# 4_Sensoren.net
KiCad netlist of a schematic drawn in Altium Designer
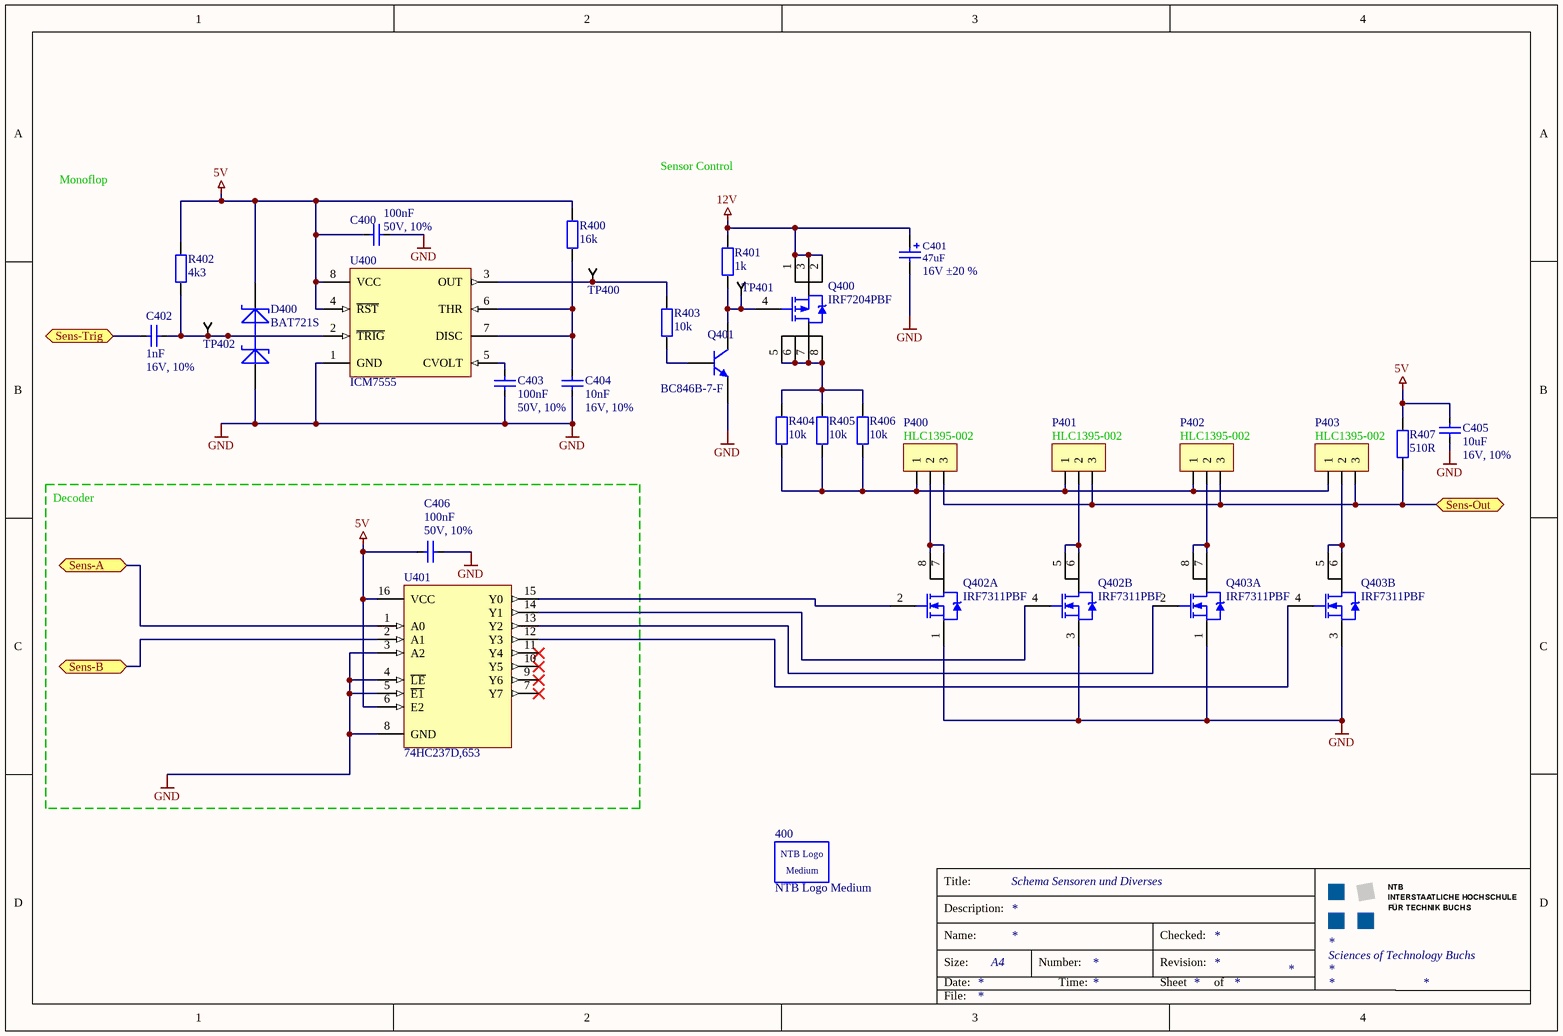
[diagram p0: 4_Sensoren.SchDoc]

(export (version "E")
  (design (tool "Eeschema 10.0.6"))
  (components
    (comp (ref "400")
      (value "NTB Logo Medium")
      (footprint "NTB Logo Medium")
      (libsource (lib "IR-Sensor") (part "NTB Logo Medium"))
    )
    (comp (ref "C400")
      (value "100nF")
      (footprint "CAP-0805[2012]")
      (description "100n 50V X7R MLCC 0805 (1608 Metric)")
      (fields (field (name "TOLERANCE") "10%") (field (name "VALADDON") "50V, 10%"))
      (libsource (lib "IR-Sensor") (part "MLCC 0805 100n 50V"))
    )
    (comp (ref "C401")
      (value "47uF")
      (footprint "CDE_CAP AVE CODE D_H")
      (description "ELKO, 47uF, 16V, CDE_AVE476M16D16T-F_AVE CODE D")
      (fields
        (field (name "MANUFACTURER") "Cornell Dubilier")
        (field (name "VALUEADDON") "16V ±20 %")
        (field (name "Comment") "AVE476M16D16T-F")
        (field (name "PUBLISHER") "Stefan Ursella, M.Eng")
      )
      (libsource (lib "IR-Sensor") (part "ELKO 47uF 16V"))
    )
    (comp (ref "C402")
      (value "1nF")
      (footprint "CAP-0805[2012]")
      (description "MLCC - SMD/SMT 0805 1000pF 16V C0G 10%")
      (fields
        (field (name "MANUFACTURER") "Vishay")
        (field (name "VALUEADDON") "16V, 10%")
        (field (name "PUBLISHER") "SCLM")
      )
      (libsource (lib "IR-Sensor") (part "MLCC 0805 1n 16V"))
    )
    (comp (ref "C403")
      (value "100nF")
      (footprint "CAP-0805[2012]")
      (description "100n 50V X7R MLCC 0805 (1608 Metric)")
      (fields (field (name "TOLERANCE") "10%") (field (name "VALADDON") "50V, 10%"))
      (libsource (lib "IR-Sensor") (part "MLCC 0805 100n 50V"))
    )
    (comp (ref "C404")
      (value "10nF")
      (footprint "CAP-0805[2012]")
      (description "10n 16V X7R MLCC 0805")
      (fields
        (field (name "MANUFACTURER") "AVX")
        (field (name "VALUEADDON") "16V, 10%")
        (field (name "PUBLISHER") "SCLM")
      )
      (libsource (lib "IR-Sensor") (part "MLCC 0805 10n 16V"))
    )
    (comp (ref "C405")
      (value "10uF")
      (footprint "CAP-1206[3216]")
      (description "10u 16V X7R MLCC 1206 (3016 Metric)")
      (fields (field (name "TOLERANCE") "10%") (field (name "VALADDON") "16V, 10%"))
      (libsource (lib "IR-Sensor") (part "MLCC 1206 10u 16V"))
    )
    (comp (ref "C406")
      (value "100nF")
      (footprint "CAP-0805[2012]")
      (description "100n 50V X7R MLCC 0805 (1608 Metric)")
      (fields (field (name "TOLERANCE") "10%") (field (name "VALADDON") "50V, 10%"))
      (libsource (lib "IR-Sensor") (part "MLCC 0805 100n 50V"))
    )
    (comp (ref "D400")
      (value "BAT721S")
      (footprint "SOT-23")
      (description "NXP  BAT721S  SCHOTTKY-DIODE, 2FACH")
      (fields (field (name "MANUFACTURER") "NXP") (field (name "PUBLISHER") "SCNP"))
      (libsource (lib "IR-Sensor") (part "BAT721S-SOT23"))
    )
    (comp (ref "P400")
      (value "3 Pin Header Buchse")
      (footprint "3PIN HEADER SOCKET 2.54MM")
      (description "3 Pin Header 2.54mm Buchse")
      (libsource (lib "IR-Sensor") (part "3 Pin Header Buchse"))
    )
    (comp (ref "P401")
      (value "3 Pin Header Buchse")
      (footprint "3PIN HEADER SOCKET 2.54MM")
      (description "3 Pin Header 2.54mm Buchse")
      (libsource (lib "IR-Sensor") (part "3 Pin Header Buchse"))
    )
    (comp (ref "P402")
      (value "3 Pin Header Buchse")
      (footprint "3PIN HEADER SOCKET 2.54MM")
      (description "3 Pin Header 2.54mm Buchse")
      (libsource (lib "IR-Sensor") (part "3 Pin Header Buchse"))
    )
    (comp (ref "P403")
      (value "3 Pin Header Buchse")
      (footprint "3PIN HEADER SOCKET 2.54MM")
      (description "3 Pin Header 2.54mm Buchse")
      (libsource (lib "IR-Sensor") (part "3 Pin Header Buchse"))
    )
    (comp (ref "Q400")
      (value "IRF7204PBF")
      (footprint "SOIC-8")
      (description "High Power P-Kanal Mosfet")
      (fields
        (field (name "MANUFACTURER") "International Rectifiers")
        (field (name "PUBLISHER") "Altium Limited")
      )
      (libsource (lib "IR-Sensor") (part "IRF7204"))
    )
    (comp (ref "Q401")
      (value "BC846B-7-F")
      (footprint "SOT-23")
      (description "NPN General-purpose Transistor")
      (fields (field (name "MANUFACTURER") "DIODES INC") (field (name "PUBLISHER") "Altium Limited"))
      (libsource (lib "IR-Sensor") (part "BC846B-SOT23"))
    )
    (comp (ref "Q402")
      (value "IRF7311PBF")
      (footprint "SOIC-8")
      (description "Dual N-Kanal Mosfet")
      (fields
        (field (name "MANUFACTURER") "International Rectifier")
        (field (name "PUBLISHER") "Altium Limited")
      )
      (libsource (lib "IR-Sensor") (part "IRF7311"))
    )
    (comp (ref "Q403")
      (value "IRF7311PBF")
      (footprint "SOIC-8")
      (description "Dual N-Kanal Mosfet")
      (fields
        (field (name "MANUFACTURER") "International Rectifier")
        (field (name "PUBLISHER") "Altium Limited")
      )
      (libsource (lib "IR-Sensor") (part "IRF7311"))
    )
    (comp (ref "R400")
      (value "16k")
      (footprint "RES-0805[2012]")
      (description "0805 (2013 Metric) 1/10 W 10K 1 Thick Film Chip Resistor")
      (fields (field (name "POWER") "1/10 W") (field (name "TOLERANCE") "1%"))
      (libsource (lib "IR-Sensor") (part "RES 0805"))
    )
    (comp (ref "R401")
      (value "1k")
      (footprint "RES-0805[2012]")
      (description "0805 (2013 Metric) 1/10 W 10K 1 Thick Film Chip Resistor")
      (fields (field (name "POWER") "1/10 W") (field (name "TOLERANCE") "1%"))
      (libsource (lib "IR-Sensor") (part "RES 0805"))
    )
    (comp (ref "R402")
      (value "4k3")
      (footprint "RES-0805[2012]")
      (description "0805 (2013 Metric) 1/10 W 10K 1 Thick Film Chip Resistor")
      (fields (field (name "POWER") "1/10 W") (field (name "TOLERANCE") "1%"))
      (libsource (lib "IR-Sensor") (part "RES 0805"))
    )
    (comp (ref "R403")
      (value "10k")
      (footprint "RES-0805[2012]")
      (description "0805 (2013 Metric) 1/10 W 10K 1 Thick Film Chip Resistor")
      (fields (field (name "POWER") "1/10 W") (field (name "TOLERANCE") "1%"))
      (libsource (lib "IR-Sensor") (part "RES 0805"))
    )
    (comp (ref "R404")
      (value "10k")
      (footprint "RES-0805[2012]")
      (description "0805 (2013 Metric) 1/10 W 10K 1 Thick Film Chip Resistor")
      (fields (field (name "POWER") "1/10 W") (field (name "TOLERANCE") "1%"))
      (libsource (lib "IR-Sensor") (part "RES 0805"))
    )
    (comp (ref "R405")
      (value "10k")
      (footprint "RES-0805[2012]")
      (description "0805 (2013 Metric) 1/10 W 10K 1 Thick Film Chip Resistor")
      (fields (field (name "POWER") "1/10 W") (field (name "TOLERANCE") "1%"))
      (libsource (lib "IR-Sensor") (part "RES 0805"))
    )
    (comp (ref "R406")
      (value "10k")
      (footprint "RES-0805[2012]")
      (description "0805 (2013 Metric) 1/10 W 10K 1 Thick Film Chip Resistor")
      (fields (field (name "POWER") "1/10 W") (field (name "TOLERANCE") "1%"))
      (libsource (lib "IR-Sensor") (part "RES 0805"))
    )
    (comp (ref "R407")
      (value "510R")
      (footprint "RES-0805[2012]")
      (description "0805 (2013 Metric) 1/10 W 10K 1 Thick Film Chip Resistor")
      (fields (field (name "POWER") "1/10 W") (field (name "TOLERANCE") "1%"))
      (libsource (lib "IR-Sensor") (part "RES 0805"))
    )
    (comp (ref "TP400")
      (value "Testpoint SMD 1206")
      (footprint "TP-SMD-1206")
      (description "Testpoint xSmall")
      (libsource (lib "IR-Sensor") (part "Testpoint SMD 1206"))
    )
    (comp (ref "TP401")
      (value "Testpoint SMD 1206")
      (footprint "TP-SMD-1206")
      (description "Testpoint xSmall")
      (libsource (lib "altium-import") (part "root_0_Testpoint SMD 1206_"))
    )
    (comp (ref "TP402")
      (value "Testpoint SMD 1206")
      (footprint "TP-SMD-1206")
      (description "Testpoint xSmall")
      (libsource (lib "IR-Sensor") (part "Testpoint SMD 1206"))
    )
    (comp (ref "U400")
      (value "ICM7555")
      (footprint "SOIC-8")
      (description "General purpose CMOS timer")
      (fields
        (field (name "MANUFACTURER") "National Semiconductor")
        (field (name "PUBLISHER") "Altium Hobart Technology Centre")
      )
      (libsource (lib "IR-Sensor") (part "ICM7555-SOIC8"))
    )
    (comp (ref "U401")
      (value "74HC237D,653")
      (footprint "SOIC-16")
      (description "3-to-8 line decoder, demultiplexer, NXP, SO16")
      (fields (field (name "MANUFACTURER") "NXP") (field (name "PUBLISHER") "SCLM"))
      (libsource (lib "IR-Sensor") (part "74HC237D-SOIC16"))
    )
  )
  (nets
    (net (code "1") (name "/Sens-A") (class "Default")
      (node (ref "U401") (pin "1") (pinfunction "A0_1") (pintype "input"))
    )
    (net (code "2") (name "/Sens-B") (class "Default")
      (node (ref "U401") (pin "2") (pinfunction "A1_2") (pintype "input"))
    )
    (net (code "3") (name "/Sens-Out") (class "Default")
      (node (ref "P400") (pin "3") (pinfunction "3_3") (pintype "passive"))
      (node (ref "P401") (pin "3") (pinfunction "3_3") (pintype "passive"))
      (node (ref "P402") (pin "3") (pinfunction "3_3") (pintype "passive"))
      (node (ref "P403") (pin "3") (pinfunction "3_3") (pintype "passive"))
      (node (ref "R407") (pin "1") (pinfunction "1_1") (pintype "passive"))
    )
    (net (code "4") (name "/Sens-Trig") (class "Default")
      (node (ref "C402") (pin "1") (pinfunction "Pos_1") (pintype "passive"))
    )
    (net (code "5") (name "5V") (class "Default")
      (node (ref "C400") (pin "1") (pinfunction "Pos_1") (pintype "passive"))
      (node (ref "C405") (pin "1") (pinfunction "Pos_1") (pintype "passive"))
      (node (ref "C406") (pin "1") (pinfunction "Pos_1") (pintype "passive"))
      (node (ref "D400") (pin "2") (pinfunction "cathode2_2") (pintype "passive"))
      (node (ref "R400") (pin "2") (pinfunction "2_2") (pintype "passive"))
      (node (ref "R402") (pin "2") (pinfunction "2_2") (pintype "passive"))
      (node (ref "R407") (pin "2") (pinfunction "2_2") (pintype "passive"))
      (node (ref "U400") (pin "4") (pinfunction "~{RST}_4") (pintype "input"))
      (node (ref "U400") (pin "8") (pinfunction "VCC_8") (pintype "power_in"))
      (node (ref "U401") (pin "16") (pinfunction "VCC_16") (pintype "power_in"))
      (node (ref "U401") (pin "6") (pinfunction "E2_6") (pintype "input"))
    )
    (net (code "6") (name "12V") (class "Default")
      (node (ref "C401") (pin "1") (pinfunction "Pos_1") (pintype "passive"))
      (node (ref "Q400") (pin "1") (pinfunction "S_1") (pintype "passive"))
      (node (ref "Q400") (pin "2") (pinfunction "S_2") (pintype "passive"))
      (node (ref "Q400") (pin "3") (pinfunction "S_3") (pintype "passive"))
      (node (ref "R401") (pin "2") (pinfunction "2_2") (pintype "passive"))
    )
    (net (code "7") (name "GND") (class "Default")
      (node (ref "C400") (pin "2") (pinfunction "Neg_2") (pintype "passive"))
      (node (ref "C401") (pin "2") (pinfunction "Neg_2") (pintype "passive"))
      (node (ref "C403") (pin "2") (pinfunction "Neg_2") (pintype "passive"))
      (node (ref "C404") (pin "2") (pinfunction "Neg_2") (pintype "passive"))
      (node (ref "C405") (pin "2") (pinfunction "Neg_2") (pintype "passive"))
      (node (ref "C406") (pin "2") (pinfunction "Neg_2") (pintype "passive"))
      (node (ref "D400") (pin "1") (pinfunction "Anode1_1") (pintype "passive"))
      (node (ref "Q401") (pin "2") (pinfunction "E_2") (pintype "passive"))
      (node (ref "Q402") (pin "1") (pinfunction "S_1") (pintype "passive"))
      (node (ref "Q402") (pin "3") (pinfunction "S_3") (pintype "passive"))
      (node (ref "Q403") (pin "1") (pinfunction "S_1") (pintype "passive"))
      (node (ref "Q403") (pin "3") (pinfunction "S_3") (pintype "passive"))
      (node (ref "U400") (pin "1") (pinfunction "GND_1") (pintype "power_in"))
      (node (ref "U401") (pin "3") (pinfunction "A2_3") (pintype "input"))
      (node (ref "U401") (pin "4") (pinfunction "LE_4") (pintype "input"))
      (node (ref "U401") (pin "5") (pinfunction "E1_5") (pintype "input"))
      (node (ref "U401") (pin "8") (pinfunction "GND_8") (pintype "power_in"))
    )
    (net (code "8") (name "Net-(C402-Neg)") (class "Default")
      (node (ref "C402") (pin "2") (pinfunction "Neg_2") (pintype "passive"))
      (node (ref "D400") (pin "3") (pinfunction "Cathode1,_anode2_3") (pintype "passive"))
      (node (ref "R402") (pin "1") (pinfunction "1_1") (pintype "passive"))
      (node (ref "TP402") (pin "1") (pinfunction "0_1") (pintype "passive"))
      (node (ref "U400") (pin "2") (pinfunction "TRIG_2") (pintype "input"))
    )
    (net (code "9") (name "Net-(C403-Pos)") (class "Default")
      (node (ref "C403") (pin "1") (pinfunction "Pos_1") (pintype "passive"))
      (node (ref "U400") (pin "5") (pinfunction "CVOLT_5") (pintype "input"))
    )
    (net (code "10") (name "Net-(C404-Pos)") (class "Default")
      (node (ref "C404") (pin "1") (pinfunction "Pos_1") (pintype "passive"))
      (node (ref "R400") (pin "1") (pinfunction "1_1") (pintype "passive"))
      (node (ref "U400") (pin "6") (pinfunction "THR_6") (pintype "input"))
      (node (ref "U400") (pin "7") (pinfunction "DISC_7") (pintype "open_collector"))
    )
    (net (code "11") (name "Net-(P400-Pad1)") (class "Default")
      (node (ref "P400") (pin "1") (pinfunction "1_1") (pintype "passive"))
      (node (ref "P401") (pin "1") (pinfunction "1_1") (pintype "passive"))
      (node (ref "P402") (pin "1") (pinfunction "1_1") (pintype "passive"))
      (node (ref "P403") (pin "1") (pinfunction "1_1") (pintype "passive"))
      (node (ref "R404") (pin "1") (pinfunction "1_1") (pintype "passive"))
      (node (ref "R405") (pin "1") (pinfunction "1_1") (pintype "passive"))
      (node (ref "R406") (pin "1") (pinfunction "1_1") (pintype "passive"))
    )
    (net (code "12") (name "Net-(P400-Pad2)") (class "Default")
      (node (ref "P400") (pin "2") (pinfunction "2_2") (pintype "passive"))
      (node (ref "Q402") (pin "7") (pinfunction "D_7") (pintype "passive"))
      (node (ref "Q402") (pin "8") (pinfunction "D_8") (pintype "passive"))
    )
    (net (code "13") (name "Net-(P401-Pad2)") (class "Default")
      (node (ref "P401") (pin "2") (pinfunction "2_2") (pintype "passive"))
      (node (ref "Q402") (pin "5") (pinfunction "D_5") (pintype "passive"))
      (node (ref "Q402") (pin "6") (pinfunction "D_6") (pintype "passive"))
    )
    (net (code "14") (name "Net-(P402-Pad2)") (class "Default")
      (node (ref "P402") (pin "2") (pinfunction "2_2") (pintype "passive"))
      (node (ref "Q403") (pin "7") (pinfunction "D_7") (pintype "passive"))
      (node (ref "Q403") (pin "8") (pinfunction "D_8") (pintype "passive"))
    )
    (net (code "15") (name "Net-(P403-Pad2)") (class "Default")
      (node (ref "P403") (pin "2") (pinfunction "2_2") (pintype "passive"))
      (node (ref "Q403") (pin "5") (pinfunction "D_5") (pintype "passive"))
      (node (ref "Q403") (pin "6") (pinfunction "D_6") (pintype "passive"))
    )
    (net (code "16") (name "Net-(Q400-D-Pad5)") (class "Default")
      (node (ref "Q400") (pin "5") (pinfunction "D_5") (pintype "passive"))
      (node (ref "Q400") (pin "6") (pinfunction "D_6") (pintype "passive"))
      (node (ref "Q400") (pin "7") (pinfunction "D_7") (pintype "passive"))
      (node (ref "Q400") (pin "8") (pinfunction "D_8") (pintype "passive"))
      (node (ref "R404") (pin "2") (pinfunction "2_2") (pintype "passive"))
      (node (ref "R405") (pin "2") (pinfunction "2_2") (pintype "passive"))
      (node (ref "R406") (pin "2") (pinfunction "2_2") (pintype "passive"))
    )
    (net (code "17") (name "Net-(Q400-G)") (class "Default")
      (node (ref "Q400") (pin "4") (pinfunction "G_4") (pintype "passive"))
      (node (ref "Q401") (pin "3") (pinfunction "C_3") (pintype "passive"))
      (node (ref "R401") (pin "1") (pinfunction "1_1") (pintype "passive"))
      (node (ref "TP401") (pin "1") (pinfunction "0_1") (pintype "passive"))
    )
    (net (code "18") (name "Net-(Q401-B)") (class "Default")
      (node (ref "Q401") (pin "1") (pinfunction "B_1") (pintype "passive"))
      (node (ref "R403") (pin "2") (pinfunction "2_2") (pintype "passive"))
    )
    (net (code "19") (name "Net-(Q402A-G)") (class "Default")
      (node (ref "Q402") (pin "2") (pinfunction "G_2") (pintype "passive"))
      (node (ref "U401") (pin "15") (pinfunction "Y0_15") (pintype "output"))
    )
    (net (code "20") (name "Net-(Q402B-G)") (class "Default")
      (node (ref "Q402") (pin "4") (pinfunction "G_4") (pintype "passive"))
      (node (ref "U401") (pin "14") (pinfunction "Y1_14") (pintype "output"))
    )
    (net (code "21") (name "Net-(Q403A-G)") (class "Default")
      (node (ref "Q403") (pin "2") (pinfunction "G_2") (pintype "passive"))
      (node (ref "U401") (pin "13") (pinfunction "Y2_13") (pintype "output"))
    )
    (net (code "22") (name "Net-(Q403B-G)") (class "Default")
      (node (ref "Q403") (pin "4") (pinfunction "G_4") (pintype "passive"))
      (node (ref "U401") (pin "12") (pinfunction "Y3_12") (pintype "output"))
    )
    (net (code "23") (name "Net-(TP400-0)") (class "Default")
      (node (ref "R403") (pin "1") (pinfunction "1_1") (pintype "passive"))
      (node (ref "TP400") (pin "1") (pinfunction "0_1") (pintype "passive"))
      (node (ref "U400") (pin "3") (pinfunction "OUT_3") (pintype "output"))
    )
    (net (code "24") (name "unconnected-(U401-Y4-Pad11)") (class "Default")
      (node (ref "U401") (pin "11") (pinfunction "Y4_11") (pintype "output+no_connect"))
    )
    (net (code "25") (name "unconnected-(U401-Y5-Pad10)") (class "Default")
      (node (ref "U401") (pin "10") (pinfunction "Y5_10") (pintype "output+no_connect"))
    )
    (net (code "26") (name "unconnected-(U401-Y6-Pad9)") (class "Default")
      (node (ref "U401") (pin "9") (pinfunction "Y6_9") (pintype "output+no_connect"))
    )
    (net (code "27") (name "unconnected-(U401-Y7-Pad7)") (class "Default")
      (node (ref "U401") (pin "7") (pinfunction "Y7_7") (pintype "output+no_connect"))
    )
  )
)
